# J-Link_ARM-OB.net
KiCad netlist of a schematic drawn in Altium Designer
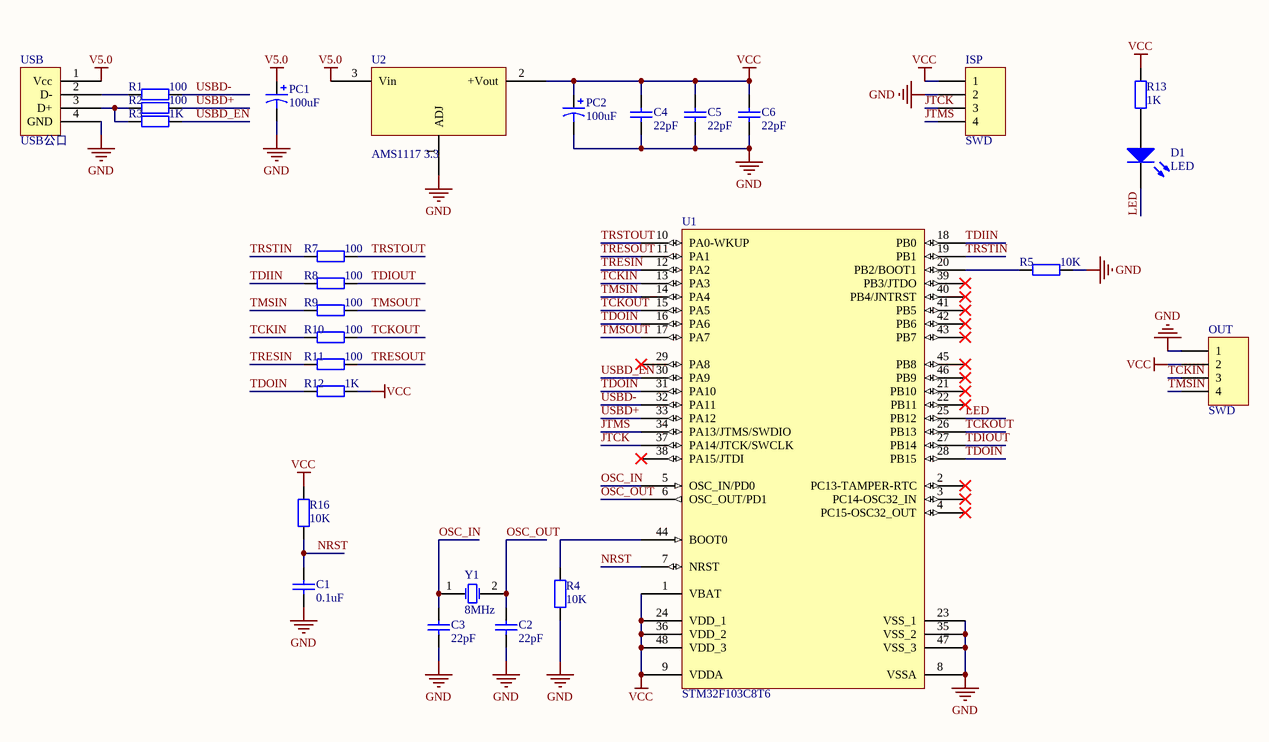
[diagram p0: J-Link ARM-OB.SchDoc]

(export (version "E")
  (design (tool "Eeschema 10.0.6"))
  (components
    (comp (ref "C1")
      (value "0.1uF")
      (footprint "Teacher:C0603")
      (description "Capacitor")
      (fields (field (name "PUBLISHER") "Altium Limited"))
      (libsource (lib "Miscellaneous Devices") (part "Cap"))
    )
    (comp (ref "C2")
      (value "22pF")
      (footprint "Teacher:C0603")
      (description "Capacitor")
      (fields (field (name "PUBLISHER") "Altium Limited"))
      (libsource (lib "Miscellaneous Devices") (part "Cap"))
    )
    (comp (ref "C3")
      (value "22pF")
      (footprint "Teacher:C0603")
      (description "Capacitor")
      (fields (field (name "PUBLISHER") "Altium Limited"))
      (libsource (lib "Miscellaneous Devices") (part "Cap"))
    )
    (comp (ref "C4")
      (value "22pF")
      (description "Capacitor")
      (fields (field (name "PUBLISHER") "Altium Limited"))
      (libsource (lib "Miscellaneous Devices") (part "Cap"))
    )
    (comp (ref "C5")
      (value "22pF")
      (description "Capacitor")
      (fields (field (name "PUBLISHER") "Altium Limited"))
      (libsource (lib "Miscellaneous Devices") (part "Cap"))
    )
    (comp (ref "C6")
      (value "22pF")
      (description "Capacitor")
      (fields (field (name "PUBLISHER") "Altium Limited"))
      (libsource (lib "Miscellaneous Devices") (part "Cap"))
    )
    (comp (ref "D1")
      (value "LED")
      (footprint "ADqun:LED0603")
      (description "Typical RED, GREEN, YELLOW, AMBER GaAs LED")
      (fields (field (name "PUBLISHER") "Altium Limited"))
      (libsource (lib "Miscellaneous Devices") (part "LED2"))
    )
    (comp (ref "ISP")
      (value "SWD")
      (footprint "HDR1X4")
      (description "Header, 4-Pin")
      (fields (field (name "PUBLISHER") "Altium Limited"))
      (libsource (lib "Miscellaneous Connectors") (part "Header 4"))
    )
    (comp (ref "OUT")
      (value "SWD")
      (footprint "HDR1X4")
      (description "Header, 4-Pin")
      (fields (field (name "PUBLISHER") "Altium Limited"))
      (libsource (lib "Miscellaneous Connectors") (part "Header 4"))
    )
    (comp (ref "PC1")
      (value "100uF")
      (footprint "Teacher:C1206A")
      (description "Polarized Capacitor (Surface Mount)")
      (fields (field (name "PUBLISHER") "Altium Limited"))
      (libsource (lib "Miscellaneous Devices") (part "Cap Pol3"))
    )
    (comp (ref "PC2")
      (value "100uF")
      (footprint "Teacher:C1206A")
      (description "Polarized Capacitor (Surface Mount)")
      (fields (field (name "PUBLISHER") "Altium Limited"))
      (libsource (lib "Miscellaneous Devices") (part "Cap Pol3"))
    )
    (comp (ref "R1")
      (value "100")
      (footprint "Teacher:R0603")
      (description "Resistor")
      (fields (field (name "PUBLISHER") "Altium Limited"))
      (libsource (lib "") (part "Res2_1"))
    )
    (comp (ref "R2")
      (value "100")
      (footprint "Teacher:R0603")
      (description "Resistor")
      (fields (field (name "PUBLISHER") "Altium Limited"))
      (libsource (lib "") (part "Res2_1"))
    )
    (comp (ref "R3")
      (value "1K")
      (footprint "Teacher:R0603")
      (description "Resistor")
      (fields (field (name "PUBLISHER") "Altium Limited"))
      (libsource (lib "") (part "Res2_1"))
    )
    (comp (ref "R4")
      (value "10K")
      (footprint "Teacher:R0603")
      (description "Resistor")
      (fields (field (name "PUBLISHER") "Altium Limited"))
      (libsource (lib "Miscellaneous Devices") (part "Res2"))
    )
    (comp (ref "R5")
      (value "10K")
      (footprint "Teacher:R0603")
      (description "Resistor")
      (fields (field (name "PUBLISHER") "Altium Limited"))
      (libsource (lib "") (part "Res2_1"))
    )
    (comp (ref "R7")
      (value "100")
      (footprint "Teacher:R0603")
      (description "Resistor")
      (fields (field (name "PUBLISHER") "Altium Limited"))
      (libsource (lib "") (part "Res2_1"))
    )
    (comp (ref "R8")
      (value "100")
      (footprint "Teacher:R0603")
      (description "Resistor")
      (fields (field (name "PUBLISHER") "Altium Limited"))
      (libsource (lib "") (part "Res2_1"))
    )
    (comp (ref "R9")
      (value "100")
      (footprint "Teacher:R0603")
      (description "Resistor")
      (fields (field (name "PUBLISHER") "Altium Limited"))
      (libsource (lib "") (part "Res2_1"))
    )
    (comp (ref "R10")
      (value "100")
      (footprint "Teacher:R0603")
      (description "Resistor")
      (fields (field (name "PUBLISHER") "Altium Limited"))
      (libsource (lib "") (part "Res2_1"))
    )
    (comp (ref "R11")
      (value "100")
      (footprint "Teacher:R0603")
      (description "Resistor")
      (fields (field (name "PUBLISHER") "Altium Limited"))
      (libsource (lib "") (part "Res2_1"))
    )
    (comp (ref "R12")
      (value "1K")
      (footprint "Teacher:R0603")
      (description "Resistor")
      (fields (field (name "PUBLISHER") "Altium Limited"))
      (libsource (lib "") (part "Res2_1"))
    )
    (comp (ref "R13")
      (value "1K")
      (footprint "Teacher:R0603")
      (description "Resistor")
      (fields (field (name "PUBLISHER") "Altium Limited"))
      (libsource (lib "") (part "Res2_2"))
    )
    (comp (ref "R16")
      (value "10K")
      (footprint "Teacher:R0603")
      (description "Resistor")
      (fields (field (name "PUBLISHER") "Altium Limited"))
      (libsource (lib "") (part "Res2_2"))
    )
    (comp (ref "U1")
      (value "STM32F103C8T6")
      (footprint "LQFP48_N")
      (description "STM32 ARM-based 32-bit MCU with 64 Kbytes Flash, 48-pin LQFP, Industrial Temperature")
      (fields (field (name "PUBLISHER") "Altium Limited"))
      (libsource (lib "ST Microcontroller 32-Bit STM32") (part "STM32F103C8T6"))
    )
    (comp (ref "U2")
      (value "AMS1117 3.3")
      (footprint "Teacher:SOT-223")
      (libsource (lib "Protel DOS Schematic Libraries") (part "LM117T"))
    )
    (comp (ref "USB") (value "USB公口") (footprint "USB-H") (libsource (lib "USB公口") (part "USB公口")))
    (comp (ref "Y1")
      (value "8MHz")
      (footprint "paul_pcb:JZ")
      (description "Crystal Oscillator")
      (fields (field (name "PUBLISHER") "Altium Limited"))
      (libsource (lib "Miscellaneous Devices") (part "XTAL"))
    )
  )
  (nets
    (net (code "1") (name "/JTCK") (class "Default")
      (node (ref "ISP") (pin "3") (pinfunction "3_3") (pintype "passive"))
      (node (ref "U1") (pin "37") (pinfunction "PA14/JTCK/SWCLK_37") (pintype "bidirectional"))
    )
    (net (code "2") (name "/JTMS") (class "Default")
      (node (ref "ISP") (pin "4") (pinfunction "4_4") (pintype "passive"))
      (node (ref "U1") (pin "34") (pinfunction "PA13/JTMS/SWDIO_34") (pintype "bidirectional"))
    )
    (net (code "3") (name "/LED") (class "Default")
      (node (ref "D1") (pin "2") (pinfunction "K_2") (pintype "passive"))
      (node (ref "U1") (pin "25") (pinfunction "PB12_25") (pintype "bidirectional"))
    )
    (net (code "4") (name "/NRST") (class "Default")
      (node (ref "C1") (pin "1") (pinfunction "1_1") (pintype "passive"))
      (node (ref "R16") (pin "1") (pinfunction "1_1") (pintype "passive"))
      (node (ref "U1") (pin "7") (pinfunction "NRST_7") (pintype "bidirectional"))
    )
    (net (code "5") (name "/OSC_IN") (class "Default")
      (node (ref "C3") (pin "1") (pinfunction "1_1") (pintype "passive"))
      (node (ref "U1") (pin "5") (pinfunction "OSC_IN/PD0_5") (pintype "input"))
      (node (ref "Y1") (pin "1") (pinfunction "OSC1_1") (pintype "passive"))
    )
    (net (code "6") (name "/OSC_OUT") (class "Default")
      (node (ref "C2") (pin "1") (pinfunction "1_1") (pintype "passive"))
      (node (ref "U1") (pin "6") (pinfunction "OSC_OUT/PD1_6") (pintype "output"))
      (node (ref "Y1") (pin "2") (pinfunction "OSC2_2") (pintype "passive"))
    )
    (net (code "7") (name "/TCKIN") (class "Default")
      (node (ref "OUT") (pin "3") (pinfunction "3_3") (pintype "passive"))
      (node (ref "R10") (pin "1") (pinfunction "1_1") (pintype "passive"))
      (node (ref "U1") (pin "13") (pinfunction "PA3_13") (pintype "bidirectional"))
    )
    (net (code "8") (name "/TCKOUT") (class "Default")
      (node (ref "R10") (pin "2") (pinfunction "2_2") (pintype "passive"))
      (node (ref "U1") (pin "15") (pinfunction "PA5_15") (pintype "bidirectional"))
      (node (ref "U1") (pin "26") (pinfunction "PB13_26") (pintype "bidirectional"))
    )
    (net (code "9") (name "/TDIIN") (class "Default")
      (node (ref "R8") (pin "1") (pinfunction "1_1") (pintype "passive"))
      (node (ref "U1") (pin "18") (pinfunction "PB0_18") (pintype "bidirectional"))
    )
    (net (code "10") (name "/TDIOUT") (class "Default")
      (node (ref "R8") (pin "2") (pinfunction "2_2") (pintype "passive"))
      (node (ref "U1") (pin "27") (pinfunction "PB14_27") (pintype "bidirectional"))
    )
    (net (code "11") (name "/TDOIN") (class "Default")
      (node (ref "R12") (pin "1") (pinfunction "1_1") (pintype "passive"))
      (node (ref "U1") (pin "16") (pinfunction "PA6_16") (pintype "bidirectional"))
      (node (ref "U1") (pin "28") (pinfunction "PB15_28") (pintype "bidirectional"))
      (node (ref "U1") (pin "31") (pinfunction "PA10_31") (pintype "bidirectional"))
    )
    (net (code "12") (name "/TMSIN") (class "Default")
      (node (ref "OUT") (pin "4") (pinfunction "4_4") (pintype "passive"))
      (node (ref "R9") (pin "1") (pinfunction "1_1") (pintype "passive"))
      (node (ref "U1") (pin "14") (pinfunction "PA4_14") (pintype "bidirectional"))
    )
    (net (code "13") (name "/TMSOUT") (class "Default")
      (node (ref "R9") (pin "2") (pinfunction "2_2") (pintype "passive"))
      (node (ref "U1") (pin "17") (pinfunction "PA7_17") (pintype "bidirectional"))
    )
    (net (code "14") (name "/TRESIN") (class "Default")
      (node (ref "R11") (pin "1") (pinfunction "1_1") (pintype "passive"))
      (node (ref "U1") (pin "12") (pinfunction "PA2_12") (pintype "bidirectional"))
    )
    (net (code "15") (name "/TRESOUT") (class "Default")
      (node (ref "R11") (pin "2") (pinfunction "2_2") (pintype "passive"))
      (node (ref "U1") (pin "11") (pinfunction "PA1_11") (pintype "bidirectional"))
    )
    (net (code "16") (name "/TRSTIN") (class "Default")
      (node (ref "R7") (pin "1") (pinfunction "1_1") (pintype "passive"))
      (node (ref "U1") (pin "19") (pinfunction "PB1_19") (pintype "bidirectional"))
    )
    (net (code "17") (name "/TRSTOUT") (class "Default")
      (node (ref "R7") (pin "2") (pinfunction "2_2") (pintype "passive"))
      (node (ref "U1") (pin "10") (pinfunction "PA0-WKUP_10") (pintype "bidirectional"))
    )
    (net (code "18") (name "/USBD+") (class "Default")
      (node (ref "R2") (pin "2") (pinfunction "2_2") (pintype "passive"))
      (node (ref "U1") (pin "33") (pinfunction "PA12_33") (pintype "bidirectional"))
    )
    (net (code "19") (name "/USBD-") (class "Default")
      (node (ref "R1") (pin "2") (pinfunction "2_2") (pintype "passive"))
      (node (ref "U1") (pin "32") (pinfunction "PA11_32") (pintype "bidirectional"))
    )
    (net (code "20") (name "/USBD_EN") (class "Default")
      (node (ref "R3") (pin "2") (pinfunction "2_2") (pintype "passive"))
      (node (ref "U1") (pin "30") (pinfunction "PA9_30") (pintype "bidirectional"))
    )
    (net (code "21") (name "GND") (class "Default")
      (node (ref "C1") (pin "2") (pinfunction "2_2") (pintype "passive"))
      (node (ref "C2") (pin "2") (pinfunction "2_2") (pintype "passive"))
      (node (ref "C3") (pin "2") (pinfunction "2_2") (pintype "passive"))
      (node (ref "C4") (pin "2") (pinfunction "2_2") (pintype "passive"))
      (node (ref "C5") (pin "2") (pinfunction "2_2") (pintype "passive"))
      (node (ref "C6") (pin "2") (pinfunction "2_2") (pintype "passive"))
      (node (ref "ISP") (pin "2") (pinfunction "2_2") (pintype "passive"))
      (node (ref "OUT") (pin "1") (pinfunction "1_1") (pintype "passive"))
      (node (ref "PC1") (pin "2") (pinfunction "2_2") (pintype "passive"))
      (node (ref "PC2") (pin "2") (pinfunction "2_2") (pintype "passive"))
      (node (ref "R4") (pin "2") (pinfunction "2_2") (pintype "passive"))
      (node (ref "R5") (pin "2") (pinfunction "2_2") (pintype "passive"))
      (node (ref "U1") (pin "23") (pinfunction "VSS_1_23") (pintype "power_in"))
      (node (ref "U1") (pin "35") (pinfunction "VSS_2_35") (pintype "power_in"))
      (node (ref "U1") (pin "47") (pinfunction "VSS_3_47") (pintype "power_in"))
      (node (ref "U1") (pin "8") (pinfunction "VSSA_8") (pintype "power_in"))
      (node (ref "U2") (pin "1") (pinfunction "ADJ_1") (pintype "passive"))
      (node (ref "USB") (pin "4") (pinfunction "GND_4") (pintype "passive"))
    )
    (net (code "22") (name "Net-(D1-A)") (class "Default")
      (node (ref "D1") (pin "1") (pinfunction "A_1") (pintype "passive"))
      (node (ref "R13") (pin "1") (pinfunction "1_1") (pintype "passive"))
    )
    (net (code "23") (name "Net-(U1-BOOT0)") (class "Default")
      (node (ref "R4") (pin "1") (pinfunction "1_1") (pintype "passive"))
      (node (ref "U1") (pin "44") (pinfunction "BOOT0_44") (pintype "input"))
    )
    (net (code "24") (name "Net-(U1-PB2{slash}BOOT1)") (class "Default")
      (node (ref "R5") (pin "1") (pinfunction "1_1") (pintype "passive"))
      (node (ref "U1") (pin "20") (pinfunction "PB2/BOOT1_20") (pintype "bidirectional"))
    )
    (net (code "25") (name "Net-(USB-D+)") (class "Default")
      (node (ref "R2") (pin "1") (pinfunction "1_1") (pintype "passive"))
      (node (ref "R3") (pin "1") (pinfunction "1_1") (pintype "passive"))
      (node (ref "USB") (pin "3") (pinfunction "D+_3") (pintype "passive"))
    )
    (net (code "26") (name "Net-(USB-D-)") (class "Default")
      (node (ref "R1") (pin "1") (pinfunction "1_1") (pintype "passive"))
      (node (ref "USB") (pin "2") (pinfunction "D-_2") (pintype "passive"))
    )
    (net (code "27") (name "V5.0") (class "Default")
      (node (ref "PC1") (pin "1") (pinfunction "1_1") (pintype "passive"))
      (node (ref "U2") (pin "3") (pinfunction "Vin_3") (pintype "passive"))
      (node (ref "USB") (pin "1") (pinfunction "Vcc_1") (pintype "passive"))
    )
    (net (code "28") (name "VCC") (class "Default")
      (node (ref "C4") (pin "1") (pinfunction "1_1") (pintype "passive"))
      (node (ref "C5") (pin "1") (pinfunction "1_1") (pintype "passive"))
      (node (ref "C6") (pin "1") (pinfunction "1_1") (pintype "passive"))
      (node (ref "ISP") (pin "1") (pinfunction "1_1") (pintype "passive"))
      (node (ref "OUT") (pin "2") (pinfunction "2_2") (pintype "passive"))
      (node (ref "PC2") (pin "1") (pinfunction "1_1") (pintype "passive"))
      (node (ref "R12") (pin "2") (pinfunction "2_2") (pintype "passive"))
      (node (ref "R13") (pin "2") (pinfunction "2_2") (pintype "passive"))
      (node (ref "R16") (pin "2") (pinfunction "2_2") (pintype "passive"))
      (node (ref "U1") (pin "1") (pinfunction "VBAT_1") (pintype "power_in"))
      (node (ref "U1") (pin "24") (pinfunction "VDD_1_24") (pintype "power_in"))
      (node (ref "U1") (pin "36") (pinfunction "VDD_2_36") (pintype "power_in"))
      (node (ref "U1") (pin "48") (pinfunction "VDD_3_48") (pintype "power_in"))
      (node (ref "U1") (pin "9") (pinfunction "VDDA_9") (pintype "power_in"))
      (node (ref "U2") (pin "2") (pinfunction "+Vout_2") (pintype "passive"))
    )
    (net (code "29") (name "unconnected-(U1-PA8-Pad29)") (class "Default")
      (node (ref "U1") (pin "29") (pinfunction "PA8_29") (pintype "bidirectional+no_connect"))
    )
    (net (code "30") (name "unconnected-(U1-PA15{slash}JTDI-Pad38)") (class "Default")
      (node (ref "U1") (pin "38") (pinfunction "PA15/JTDI_38") (pintype "bidirectional+no_connect"))
    )
    (net (code "31") (name "unconnected-(U1-PB3{slash}JTDO-Pad39)") (class "Default")
      (node (ref "U1") (pin "39") (pinfunction "PB3/JTDO_39") (pintype "bidirectional+no_connect"))
    )
    (net (code "32") (name "unconnected-(U1-PB4{slash}JNTRST-Pad40)") (class "Default")
      (node (ref "U1") (pin "40") (pinfunction "PB4/JNTRST_40") (pintype "bidirectional+no_connect"))
    )
    (net (code "33") (name "unconnected-(U1-PB5-Pad41)") (class "Default")
      (node (ref "U1") (pin "41") (pinfunction "PB5_41") (pintype "bidirectional+no_connect"))
    )
    (net (code "34") (name "unconnected-(U1-PB6-Pad42)") (class "Default")
      (node (ref "U1") (pin "42") (pinfunction "PB6_42") (pintype "bidirectional+no_connect"))
    )
    (net (code "35") (name "unconnected-(U1-PB7-Pad43)") (class "Default")
      (node (ref "U1") (pin "43") (pinfunction "PB7_43") (pintype "bidirectional+no_connect"))
    )
    (net (code "36") (name "unconnected-(U1-PB8-Pad45)") (class "Default")
      (node (ref "U1") (pin "45") (pinfunction "PB8_45") (pintype "bidirectional+no_connect"))
    )
    (net (code "37") (name "unconnected-(U1-PB9-Pad46)") (class "Default")
      (node (ref "U1") (pin "46") (pinfunction "PB9_46") (pintype "bidirectional+no_connect"))
    )
    (net (code "38") (name "unconnected-(U1-PB10-Pad21)") (class "Default")
      (node (ref "U1") (pin "21") (pinfunction "PB10_21") (pintype "bidirectional+no_connect"))
    )
    (net (code "39") (name "unconnected-(U1-PB11-Pad22)") (class "Default")
      (node (ref "U1") (pin "22") (pinfunction "PB11_22") (pintype "bidirectional+no_connect"))
    )
    (net (code "40") (name "unconnected-(U1-PC13-TAMPER-RTC-Pad2)") (class "Default")
      (node (ref "U1") (pin "2") (pinfunction "PC13-TAMPER-RTC_2") (pintype "bidirectional+no_connect"))
    )
    (net (code "41") (name "unconnected-(U1-PC14-OSC32_IN-Pad3)") (class "Default")
      (node (ref "U1") (pin "3") (pinfunction "PC14-OSC32_IN_3") (pintype "bidirectional+no_connect"))
    )
    (net (code "42") (name "unconnected-(U1-PC15-OSC32_OUT-Pad4)") (class "Default")
      (node (ref "U1") (pin "4") (pinfunction "PC15-OSC32_OUT_4") (pintype "bidirectional+no_connect"))
    )
  )
)
